# InterfazDeProgramaacion.net
KiCad netlist of a schematic drawn in Altium Designer
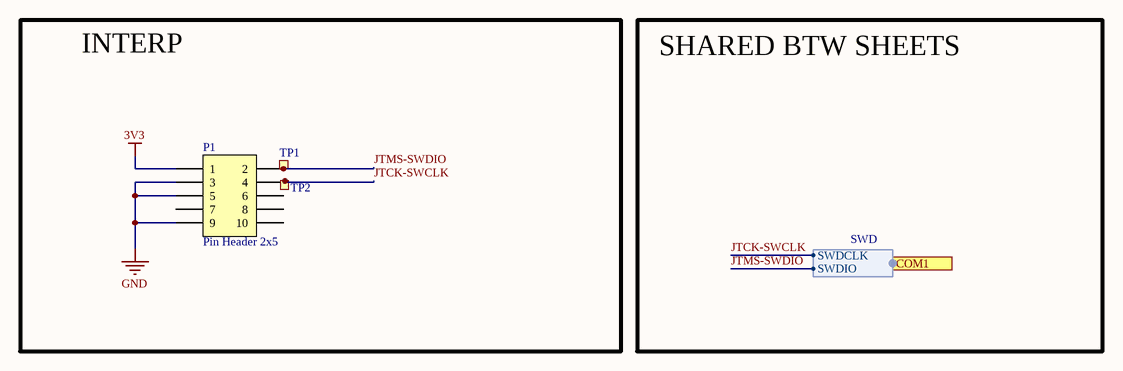
[diagram p0: InterfazDeProgramaacion.SchDoc]

(export (version "E")
  (design (tool "Eeschema 10.0.6"))
  (components
    (comp (ref "P1")
      (value "Pin Header 2x5")
      (footprint "HDR_2x5-SMD-1.27mm-ANG")
      (description "Pin Header 2x5, 1.27mm (50mil)")
      (fields
        (field (name "PART NUMBER") "Pin Header 2x5 SMD, 1.27mm, Angled")
        (field (name "MANUFACTURER") "Samtec")
        (field (name "PUBLISHER") "Nordic Semiconductor")
      )
      (libsource (lib "FEEL2020") (part "Pin Header 2x5 SMD, 1.27mm, Angled"))
    )
    (comp (ref "TP1")
      (value "Ø1.0mm,SMD")
      (footprint "TP_SMD_Ø1.0mm")
      (description "1.0mm circular SMD testpad")
      (fields
        (field (name "PART NUMBER") "TP_SMD_Ø1.0MM")
        (field (name "MANUFACTURER") "Nordic Semiconductor")
        (field (name "PUBLISHER") "Nordic Semiconductor")
      )
      (libsource (lib "") (part "TP_SMD_Ø1.0MM_1"))
    )
    (comp (ref "TP2")
      (value "Ø1.0mm,SMD")
      (footprint "TP_SMD_Ø1.0mm")
      (description "1.0mm circular SMD testpad")
      (fields
        (field (name "PART NUMBER") "TP_SMD_Ø1.0MM")
        (field (name "MANUFACTURER") "Nordic Semiconductor")
        (field (name "PUBLISHER") "Nordic Semiconductor")
      )
      (libsource (lib "FEEL2020") (part "TP_SMD_Ø1.0MM"))
    )
  )
  (nets
    (net (code "2") (name "/JTCK-SWCLK") (class "Default")
      (node (ref "P1") (pin "4") (pinfunction "4_4") (pintype "passive"))
      (node (ref "TP2") (pin "1") (pinfunction "1_1") (pintype "passive"))
    )
    (net (code "3") (name "/JTMS-SWDIO") (class "Default")
      (node (ref "P1") (pin "2") (pinfunction "2_2") (pintype "passive"))
      (node (ref "TP1") (pin "1") (pinfunction "1_1") (pintype "passive"))
    )
    (net (code "5") (name "3V3") (class "Default")
      (node (ref "P1") (pin "1") (pinfunction "1_1") (pintype "passive"))
    )
    (net (code "6") (name "GND") (class "Default")
      (node (ref "P1") (pin "3") (pinfunction "3_3") (pintype "passive"))
      (node (ref "P1") (pin "5") (pinfunction "5_5") (pintype "passive"))
      (node (ref "P1") (pin "9") (pinfunction "9_9") (pintype "passive"))
    )
    (net (code "7") (name "unconnected-(P1-Pad6)") (class "Default")
      (node (ref "P1") (pin "6") (pinfunction "6_6") (pintype "passive"))
    )
    (net (code "8") (name "unconnected-(P1-Pad7)") (class "Default")
      (node (ref "P1") (pin "7") (pinfunction "7_7") (pintype "passive"))
    )
    (net (code "9") (name "unconnected-(P1-Pad8)") (class "Default")
      (node (ref "P1") (pin "8") (pinfunction "8_8") (pintype "passive"))
    )
    (net (code "10") (name "unconnected-(P1-Pad10)") (class "Default")
      (node (ref "P1") (pin "10") (pinfunction "10_10") (pintype "passive"))
    )
  )
)
